# 1A20J19_1A21J11_B.net
KiCad netlist of a schematic drawn in Altium Designer
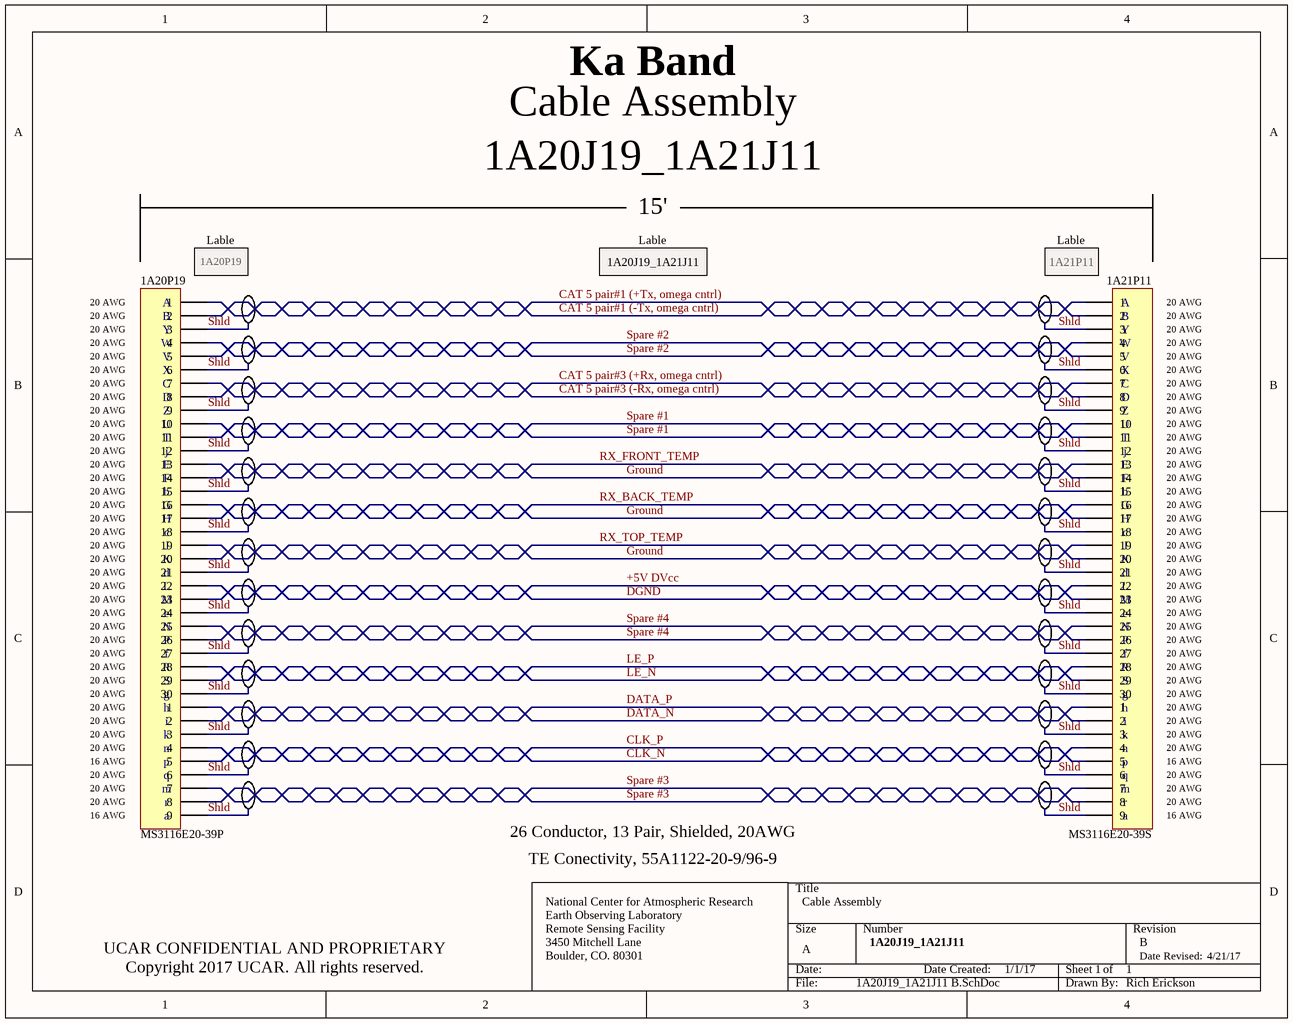
[diagram p0: 1A20J19_1A21J11 B.SchDoc]

(export (version "E")
  (design (tool "Eeschema 10.0.6"))
  (components
    (comp (ref "1A20P19")
      (value "MS3126E18-32P")
      (footprint "HDR1X30")
      (description "Header, 30-Pin")
      (fields (field (name "PUBLISHER") "Altium Limited"))
      (libsource (lib "") (part "Header 30_1"))
    )
    (comp (ref "1A20P19a")
      (value "MS3116E20-39P")
      (footprint "HDR1X9")
      (description "Header, 9-Pin")
      (fields (field (name "PUBLISHER") "Altium Limited"))
      (libsource (lib "Miscellaneous Connectors") (part "Header 9"))
    )
    (comp (ref "1A21P11")
      (value "MS3126E18-32S")
      (footprint "HDR1X30")
      (description "Header, 30-Pin")
      (fields (field (name "PUBLISHER") "Altium Limited"))
      (libsource (lib "Miscellaneous Connectors") (part "Header 30"))
    )
    (comp (ref "1A21P11a")
      (value "MS3116E20-39S")
      (footprint "HDR1X9")
      (description "Header, 9-Pin")
      (fields (field (name "PUBLISHER") "Altium Limited"))
      (libsource (lib "") (part "Header 9_1"))
    )
  )
  (nets
    (net (code "1") (name "/+5V DVcc") (class "Default")
      (node (ref "1A20P19") (pin "22") (pinfunction "22_22") (pintype "passive"))
      (node (ref "1A21P11") (pin "22") (pinfunction "22_22") (pintype "passive"))
    )
    (net (code "2") (name "/CAT 5 pair#1 (+Tx, omega cntrl)") (class "Default")
      (node (ref "1A20P19") (pin "1") (pinfunction "1_1") (pintype "passive"))
      (node (ref "1A21P11") (pin "1") (pinfunction "1_1") (pintype "passive"))
    )
    (net (code "3") (name "/CAT 5 pair#1 (-Tx, omega cntrl)") (class "Default")
      (node (ref "1A20P19") (pin "2") (pinfunction "2_2") (pintype "passive"))
      (node (ref "1A21P11") (pin "2") (pinfunction "2_2") (pintype "passive"))
    )
    (net (code "4") (name "/CAT 5 pair#3 (+Rx, omega cntrl)") (class "Default")
      (node (ref "1A20P19") (pin "7") (pinfunction "7_7") (pintype "passive"))
      (node (ref "1A21P11") (pin "7") (pinfunction "7_7") (pintype "passive"))
    )
    (net (code "5") (name "/CAT 5 pair#3 (-Rx, omega cntrl)") (class "Default")
      (node (ref "1A20P19") (pin "8") (pinfunction "8_8") (pintype "passive"))
      (node (ref "1A21P11") (pin "8") (pinfunction "8_8") (pintype "passive"))
    )
    (net (code "6") (name "/CLK_N") (class "Default")
      (node (ref "1A20P19a") (pin "5") (pinfunction "5_5") (pintype "passive"))
      (node (ref "1A21P11a") (pin "5") (pinfunction "5_5") (pintype "passive"))
    )
    (net (code "7") (name "/CLK_P") (class "Default")
      (node (ref "1A20P19a") (pin "4") (pinfunction "4_4") (pintype "passive"))
      (node (ref "1A21P11a") (pin "4") (pinfunction "4_4") (pintype "passive"))
    )
    (net (code "8") (name "/DATA_N") (class "Default")
      (node (ref "1A20P19a") (pin "2") (pinfunction "2_2") (pintype "passive"))
      (node (ref "1A21P11a") (pin "2") (pinfunction "2_2") (pintype "passive"))
    )
    (net (code "9") (name "/DATA_P") (class "Default")
      (node (ref "1A20P19a") (pin "1") (pinfunction "1_1") (pintype "passive"))
      (node (ref "1A21P11a") (pin "1") (pinfunction "1_1") (pintype "passive"))
    )
    (net (code "10") (name "/DGND") (class "Default")
      (node (ref "1A20P19") (pin "23") (pinfunction "23_23") (pintype "passive"))
      (node (ref "1A21P11") (pin "23") (pinfunction "23_23") (pintype "passive"))
    )
    (net (code "11") (name "/Ground") (class "Default")
      (node (ref "1A20P19") (pin "14") (pinfunction "14_14") (pintype "passive"))
      (node (ref "1A20P19") (pin "17") (pinfunction "17_17") (pintype "passive"))
      (node (ref "1A20P19") (pin "20") (pinfunction "20_20") (pintype "passive"))
      (node (ref "1A21P11") (pin "14") (pinfunction "14_14") (pintype "passive"))
      (node (ref "1A21P11") (pin "17") (pinfunction "17_17") (pintype "passive"))
      (node (ref "1A21P11") (pin "20") (pinfunction "20_20") (pintype "passive"))
    )
    (net (code "12") (name "/LE_N") (class "Default")
      (node (ref "1A20P19") (pin "29") (pinfunction "29_29") (pintype "passive"))
      (node (ref "1A21P11") (pin "29") (pinfunction "29_29") (pintype "passive"))
    )
    (net (code "13") (name "/LE_P") (class "Default")
      (node (ref "1A20P19") (pin "28") (pinfunction "28_28") (pintype "passive"))
      (node (ref "1A21P11") (pin "28") (pinfunction "28_28") (pintype "passive"))
    )
    (net (code "14") (name "/RX_BACK_TEMP") (class "Default")
      (node (ref "1A20P19") (pin "16") (pinfunction "16_16") (pintype "passive"))
      (node (ref "1A21P11") (pin "16") (pinfunction "16_16") (pintype "passive"))
    )
    (net (code "15") (name "/RX_FRONT_TEMP") (class "Default")
      (node (ref "1A20P19") (pin "13") (pinfunction "13_13") (pintype "passive"))
      (node (ref "1A21P11") (pin "13") (pinfunction "13_13") (pintype "passive"))
    )
    (net (code "16") (name "/RX_TOP_TEMP") (class "Default")
      (node (ref "1A20P19") (pin "19") (pinfunction "19_19") (pintype "passive"))
      (node (ref "1A21P11") (pin "19") (pinfunction "19_19") (pintype "passive"))
    )
    (net (code "17") (name "/Shld") (class "Default")
      (node (ref "1A20P19") (pin "12") (pinfunction "12_12") (pintype "passive"))
      (node (ref "1A20P19") (pin "15") (pinfunction "15_15") (pintype "passive"))
      (node (ref "1A20P19") (pin "18") (pinfunction "18_18") (pintype "passive"))
      (node (ref "1A20P19") (pin "21") (pinfunction "21_21") (pintype "passive"))
      (node (ref "1A20P19") (pin "24") (pinfunction "24_24") (pintype "passive"))
      (node (ref "1A20P19") (pin "27") (pinfunction "27_27") (pintype "passive"))
      (node (ref "1A20P19") (pin "3") (pinfunction "3_3") (pintype "passive"))
      (node (ref "1A20P19") (pin "30") (pinfunction "30_30") (pintype "passive"))
      (node (ref "1A20P19") (pin "6") (pinfunction "6_6") (pintype "passive"))
      (node (ref "1A20P19") (pin "9") (pinfunction "9_9") (pintype "passive"))
      (node (ref "1A20P19a") (pin "3") (pinfunction "3_3") (pintype "passive"))
      (node (ref "1A20P19a") (pin "6") (pinfunction "6_6") (pintype "passive"))
      (node (ref "1A20P19a") (pin "9") (pinfunction "9_9") (pintype "passive"))
      (node (ref "1A21P11") (pin "12") (pinfunction "12_12") (pintype "passive"))
      (node (ref "1A21P11") (pin "15") (pinfunction "15_15") (pintype "passive"))
      (node (ref "1A21P11") (pin "18") (pinfunction "18_18") (pintype "passive"))
      (node (ref "1A21P11") (pin "21") (pinfunction "21_21") (pintype "passive"))
      (node (ref "1A21P11") (pin "24") (pinfunction "24_24") (pintype "passive"))
      (node (ref "1A21P11") (pin "27") (pinfunction "27_27") (pintype "passive"))
      (node (ref "1A21P11") (pin "3") (pinfunction "3_3") (pintype "passive"))
      (node (ref "1A21P11") (pin "30") (pinfunction "30_30") (pintype "passive"))
      (node (ref "1A21P11") (pin "6") (pinfunction "6_6") (pintype "passive"))
      (node (ref "1A21P11") (pin "9") (pinfunction "9_9") (pintype "passive"))
      (node (ref "1A21P11a") (pin "3") (pinfunction "3_3") (pintype "passive"))
      (node (ref "1A21P11a") (pin "6") (pinfunction "6_6") (pintype "passive"))
      (node (ref "1A21P11a") (pin "9") (pinfunction "9_9") (pintype "passive"))
    )
    (net (code "18") (name "/Spare #1") (class "Default")
      (node (ref "1A20P19") (pin "10") (pinfunction "10_10") (pintype "passive"))
      (node (ref "1A20P19") (pin "11") (pinfunction "11_11") (pintype "passive"))
      (node (ref "1A21P11") (pin "10") (pinfunction "10_10") (pintype "passive"))
      (node (ref "1A21P11") (pin "11") (pinfunction "11_11") (pintype "passive"))
    )
    (net (code "19") (name "/Spare #2") (class "Default")
      (node (ref "1A20P19") (pin "4") (pinfunction "4_4") (pintype "passive"))
      (node (ref "1A20P19") (pin "5") (pinfunction "5_5") (pintype "passive"))
      (node (ref "1A21P11") (pin "4") (pinfunction "4_4") (pintype "passive"))
      (node (ref "1A21P11") (pin "5") (pinfunction "5_5") (pintype "passive"))
    )
    (net (code "20") (name "/Spare #3") (class "Default")
      (node (ref "1A20P19a") (pin "7") (pinfunction "7_7") (pintype "passive"))
      (node (ref "1A20P19a") (pin "8") (pinfunction "8_8") (pintype "passive"))
      (node (ref "1A21P11a") (pin "7") (pinfunction "7_7") (pintype "passive"))
      (node (ref "1A21P11a") (pin "8") (pinfunction "8_8") (pintype "passive"))
    )
    (net (code "21") (name "/Spare #4") (class "Default")
      (node (ref "1A20P19") (pin "25") (pinfunction "25_25") (pintype "passive"))
      (node (ref "1A20P19") (pin "26") (pinfunction "26_26") (pintype "passive"))
      (node (ref "1A21P11") (pin "25") (pinfunction "25_25") (pintype "passive"))
      (node (ref "1A21P11") (pin "26") (pinfunction "26_26") (pintype "passive"))
    )
  )
)
